# 3__Connectors___IO.net
KiCad netlist of a schematic drawn in Altium Designer
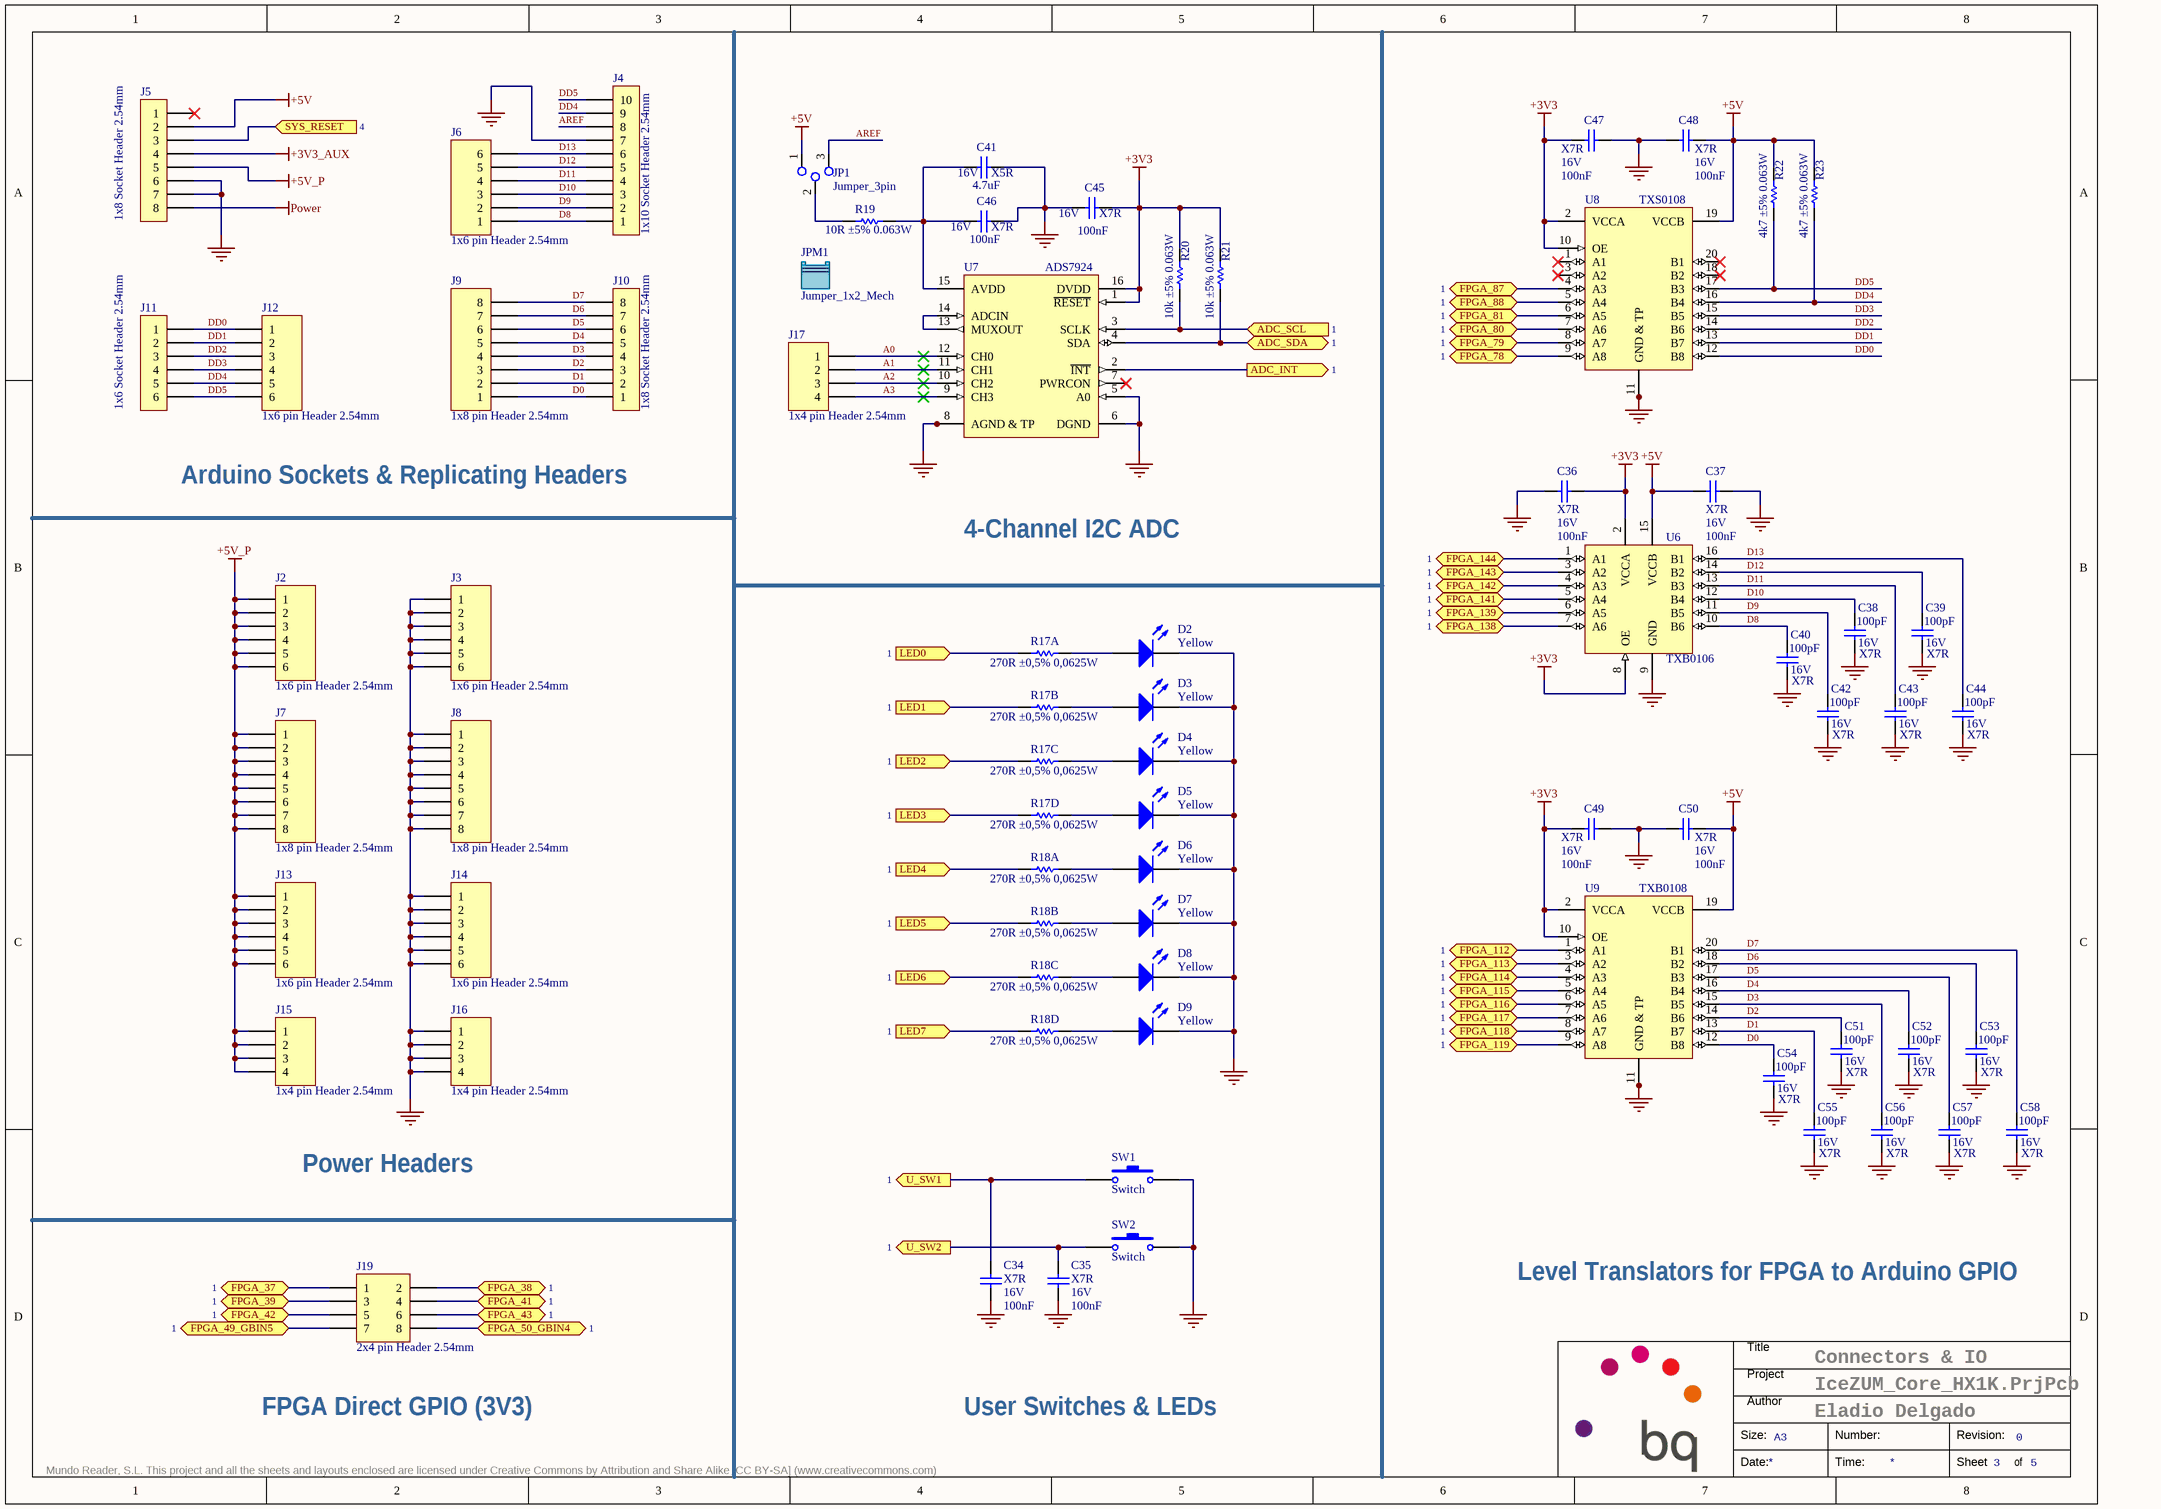
[diagram p0: [3]_Connectors_&_IO.SchDoc]

(export (version "E")
  (design (tool "Eeschema 10.0.6"))
  (components
    (comp (ref "C34")
      (value "Capacitor")
      (footprint "C0402")
      (description "Capacitor SMD")
      (fields
        (field (name "DIELECTRIC") "X7R")
        (field (name "VOLTAGE") "16V")
        (field (name "CAPACITANCE") "100nF")
        (field (name "PART NUMBER") "C0402_100nF_16V_±10%")
        (field (name "TOLERANCE") "±10%")
      )
      (libsource (lib "Pasives_Capacitor_SMD") (part "Capacitor"))
    )
    (comp (ref "C35")
      (value "Capacitor")
      (footprint "C0402")
      (description "Capacitor SMD")
      (fields
        (field (name "DIELECTRIC") "X7R")
        (field (name "VOLTAGE") "16V")
        (field (name "CAPACITANCE") "100nF")
        (field (name "PART NUMBER") "C0402_100nF_16V_±10%")
        (field (name "TOLERANCE") "±10%")
      )
      (libsource (lib "Pasives_Capacitor_SMD") (part "Capacitor"))
    )
    (comp (ref "C36")
      (value "Capacitor")
      (footprint "C0402")
      (description "Capacitor SMD")
      (fields
        (field (name "DIELECTRIC") "X7R")
        (field (name "VOLTAGE") "16V")
        (field (name "CAPACITANCE") "100nF")
        (field (name "PART NUMBER") "C0402_100nF_16V_±10%")
        (field (name "TOLERANCE") "±10%")
      )
      (libsource (lib "Pasives_Capacitor_SMD") (part "Capacitor"))
    )
    (comp (ref "C37")
      (value "Capacitor")
      (footprint "C0402")
      (description "Capacitor SMD")
      (fields
        (field (name "DIELECTRIC") "X7R")
        (field (name "VOLTAGE") "16V")
        (field (name "CAPACITANCE") "100nF")
        (field (name "PART NUMBER") "C0402_100nF_16V_±10%")
        (field (name "TOLERANCE") "±10%")
      )
      (libsource (lib "Pasives_Capacitor_SMD") (part "Capacitor"))
    )
    (comp (ref "C38")
      (value "Capacitor")
      (footprint "C0402")
      (description "Capacitor SMD")
      (fields
        (field (name "DIELECTRIC") "X7R")
        (field (name "VOLTAGE") "16V")
        (field (name "CAPACITANCE") "100pF")
        (field (name "PART NUMBER") "C0402_100pF_16V_±10%")
        (field (name "TOLERANCE") "±10%")
      )
      (libsource (lib "Pasives_Capacitor_SMD") (part "Capacitor"))
    )
    (comp (ref "C39")
      (value "Capacitor")
      (footprint "C0402")
      (description "Capacitor SMD")
      (fields
        (field (name "DIELECTRIC") "X7R")
        (field (name "VOLTAGE") "16V")
        (field (name "CAPACITANCE") "100pF")
        (field (name "PART NUMBER") "C0402_100pF_16V_±10%")
        (field (name "TOLERANCE") "±10%")
      )
      (libsource (lib "Pasives_Capacitor_SMD") (part "Capacitor"))
    )
    (comp (ref "C40")
      (value "Capacitor")
      (footprint "C0402")
      (description "Capacitor SMD")
      (fields
        (field (name "DIELECTRIC") "X7R")
        (field (name "VOLTAGE") "16V")
        (field (name "CAPACITANCE") "100pF")
        (field (name "PART NUMBER") "C0402_100pF_16V_±10%")
        (field (name "TOLERANCE") "±10%")
      )
      (libsource (lib "Pasives_Capacitor_SMD") (part "Capacitor"))
    )
    (comp (ref "C41")
      (value "Capacitor")
      (footprint "C0603")
      (description "Capacitor SMD")
      (fields
        (field (name "DIELECTRIC") "X5R")
        (field (name "VOLTAGE") "16V")
        (field (name "CAPACITANCE") "4.7uF")
        (field (name "PART NUMBER") "C0603_4.7uF_16V_±10%")
        (field (name "TOLERANCE") "±10%")
      )
      (libsource (lib "Pasives_Capacitor_SMD") (part "Capacitor"))
    )
    (comp (ref "C42")
      (value "Capacitor")
      (footprint "C0402")
      (description "Capacitor SMD")
      (fields
        (field (name "DIELECTRIC") "X7R")
        (field (name "VOLTAGE") "16V")
        (field (name "CAPACITANCE") "100pF")
        (field (name "PART NUMBER") "C0402_100pF_16V_±10%")
        (field (name "TOLERANCE") "±10%")
      )
      (libsource (lib "Pasives_Capacitor_SMD") (part "Capacitor"))
    )
    (comp (ref "C43")
      (value "Capacitor")
      (footprint "C0402")
      (description "Capacitor SMD")
      (fields
        (field (name "DIELECTRIC") "X7R")
        (field (name "VOLTAGE") "16V")
        (field (name "CAPACITANCE") "100pF")
        (field (name "PART NUMBER") "C0402_100pF_16V_±10%")
        (field (name "TOLERANCE") "±10%")
      )
      (libsource (lib "Pasives_Capacitor_SMD") (part "Capacitor"))
    )
    (comp (ref "C44")
      (value "Capacitor")
      (footprint "C0402")
      (description "Capacitor SMD")
      (fields
        (field (name "DIELECTRIC") "X7R")
        (field (name "VOLTAGE") "16V")
        (field (name "CAPACITANCE") "100pF")
        (field (name "PART NUMBER") "C0402_100pF_16V_±10%")
        (field (name "TOLERANCE") "±10%")
      )
      (libsource (lib "Pasives_Capacitor_SMD") (part "Capacitor"))
    )
    (comp (ref "C45")
      (value "Capacitor")
      (footprint "C0402")
      (description "Capacitor SMD")
      (fields
        (field (name "DIELECTRIC") "X7R")
        (field (name "VOLTAGE") "16V")
        (field (name "CAPACITANCE") "100nF")
        (field (name "PART NUMBER") "C0402_100nF_16V_±10%")
        (field (name "TOLERANCE") "±10%")
      )
      (libsource (lib "Pasives_Capacitor_SMD") (part "Capacitor"))
    )
    (comp (ref "C46")
      (value "Capacitor")
      (footprint "C0402")
      (description "Capacitor SMD")
      (fields
        (field (name "DIELECTRIC") "X7R")
        (field (name "VOLTAGE") "16V")
        (field (name "CAPACITANCE") "100nF")
        (field (name "PART NUMBER") "C0402_100nF_16V_±10%")
        (field (name "TOLERANCE") "±10%")
      )
      (libsource (lib "Pasives_Capacitor_SMD") (part "Capacitor"))
    )
    (comp (ref "C47")
      (value "Capacitor")
      (footprint "C0402")
      (description "Capacitor SMD")
      (fields
        (field (name "DIELECTRIC") "X7R")
        (field (name "VOLTAGE") "16V")
        (field (name "CAPACITANCE") "100nF")
        (field (name "PART NUMBER") "C0402_100nF_16V_±10%")
        (field (name "TOLERANCE") "±10%")
      )
      (libsource (lib "Pasives_Capacitor_SMD") (part "Capacitor"))
    )
    (comp (ref "C48")
      (value "Capacitor")
      (footprint "C0402")
      (description "Capacitor SMD")
      (fields
        (field (name "DIELECTRIC") "X7R")
        (field (name "VOLTAGE") "16V")
        (field (name "CAPACITANCE") "100nF")
        (field (name "PART NUMBER") "C0402_100nF_16V_±10%")
        (field (name "TOLERANCE") "±10%")
      )
      (libsource (lib "Pasives_Capacitor_SMD") (part "Capacitor"))
    )
    (comp (ref "C49")
      (value "Capacitor")
      (footprint "C0402")
      (description "Capacitor SMD")
      (fields
        (field (name "DIELECTRIC") "X7R")
        (field (name "VOLTAGE") "16V")
        (field (name "CAPACITANCE") "100nF")
        (field (name "PART NUMBER") "C0402_100nF_16V_±10%")
        (field (name "TOLERANCE") "±10%")
      )
      (libsource (lib "Pasives_Capacitor_SMD") (part "Capacitor"))
    )
    (comp (ref "C50")
      (value "Capacitor")
      (footprint "C0402")
      (description "Capacitor SMD")
      (fields
        (field (name "DIELECTRIC") "X7R")
        (field (name "VOLTAGE") "16V")
        (field (name "CAPACITANCE") "100nF")
        (field (name "PART NUMBER") "C0402_100nF_16V_±10%")
        (field (name "TOLERANCE") "±10%")
      )
      (libsource (lib "Pasives_Capacitor_SMD") (part "Capacitor"))
    )
    (comp (ref "C51")
      (value "Capacitor")
      (footprint "C0402")
      (description "Capacitor SMD")
      (fields
        (field (name "DIELECTRIC") "X7R")
        (field (name "VOLTAGE") "16V")
        (field (name "CAPACITANCE") "100pF")
        (field (name "PART NUMBER") "C0402_100pF_16V_±10%")
        (field (name "TOLERANCE") "±10%")
      )
      (libsource (lib "Pasives_Capacitor_SMD") (part "Capacitor"))
    )
    (comp (ref "C52")
      (value "Capacitor")
      (footprint "C0402")
      (description "Capacitor SMD")
      (fields
        (field (name "DIELECTRIC") "X7R")
        (field (name "VOLTAGE") "16V")
        (field (name "CAPACITANCE") "100pF")
        (field (name "PART NUMBER") "C0402_100pF_16V_±10%")
        (field (name "TOLERANCE") "±10%")
      )
      (libsource (lib "Pasives_Capacitor_SMD") (part "Capacitor"))
    )
    (comp (ref "C53")
      (value "Capacitor")
      (footprint "C0402")
      (description "Capacitor SMD")
      (fields
        (field (name "DIELECTRIC") "X7R")
        (field (name "VOLTAGE") "16V")
        (field (name "CAPACITANCE") "100pF")
        (field (name "PART NUMBER") "C0402_100pF_16V_±10%")
        (field (name "TOLERANCE") "±10%")
      )
      (libsource (lib "Pasives_Capacitor_SMD") (part "Capacitor"))
    )
    (comp (ref "C54")
      (value "Capacitor")
      (footprint "C0402")
      (description "Capacitor SMD")
      (fields
        (field (name "DIELECTRIC") "X7R")
        (field (name "VOLTAGE") "16V")
        (field (name "CAPACITANCE") "100pF")
        (field (name "PART NUMBER") "C0402_100pF_16V_±10%")
        (field (name "TOLERANCE") "±10%")
      )
      (libsource (lib "Pasives_Capacitor_SMD") (part "Capacitor"))
    )
    (comp (ref "C55")
      (value "Capacitor")
      (footprint "C0402")
      (description "Capacitor SMD")
      (fields
        (field (name "DIELECTRIC") "X7R")
        (field (name "VOLTAGE") "16V")
        (field (name "CAPACITANCE") "100pF")
        (field (name "PART NUMBER") "C0402_100pF_16V_±10%")
        (field (name "TOLERANCE") "±10%")
      )
      (libsource (lib "Pasives_Capacitor_SMD") (part "Capacitor"))
    )
    (comp (ref "C56")
      (value "Capacitor")
      (footprint "C0402")
      (description "Capacitor SMD")
      (fields
        (field (name "DIELECTRIC") "X7R")
        (field (name "VOLTAGE") "16V")
        (field (name "CAPACITANCE") "100pF")
        (field (name "PART NUMBER") "C0402_100pF_16V_±10%")
        (field (name "TOLERANCE") "±10%")
      )
      (libsource (lib "Pasives_Capacitor_SMD") (part "Capacitor"))
    )
    (comp (ref "C57")
      (value "Capacitor")
      (footprint "C0402")
      (description "Capacitor SMD")
      (fields
        (field (name "DIELECTRIC") "X7R")
        (field (name "VOLTAGE") "16V")
        (field (name "CAPACITANCE") "100pF")
        (field (name "PART NUMBER") "C0402_100pF_16V_±10%")
        (field (name "TOLERANCE") "±10%")
      )
      (libsource (lib "Pasives_Capacitor_SMD") (part "Capacitor"))
    )
    (comp (ref "C58")
      (value "Capacitor")
      (footprint "C0402")
      (description "Capacitor SMD")
      (fields
        (field (name "DIELECTRIC") "X7R")
        (field (name "VOLTAGE") "16V")
        (field (name "CAPACITANCE") "100pF")
        (field (name "PART NUMBER") "C0402_100pF_16V_±10%")
        (field (name "TOLERANCE") "±10%")
      )
      (libsource (lib "Pasives_Capacitor_SMD") (part "Capacitor"))
    )
    (comp (ref "D2")
      (value "Yellow")
      (footprint "LED0603")
      (description "LED")
      (fields (field (name "PART NUMBER") "LY Q971-H1L2-36") (field (name "MANUFACTURER") "OSRAM Opto"))
      (libsource (lib "Optoelectronics") (part "LED"))
    )
    (comp (ref "D3")
      (value "Yellow")
      (footprint "LED0603")
      (description "LED")
      (fields (field (name "PART NUMBER") "LY Q971-H1L2-36") (field (name "MANUFACTURER") "OSRAM Opto"))
      (libsource (lib "Optoelectronics") (part "LED"))
    )
    (comp (ref "D4")
      (value "Yellow")
      (footprint "LED0603")
      (description "LED")
      (fields (field (name "PART NUMBER") "LY Q971-H1L2-36") (field (name "MANUFACTURER") "OSRAM Opto"))
      (libsource (lib "Optoelectronics") (part "LED"))
    )
    (comp (ref "D5")
      (value "Yellow")
      (footprint "LED0603")
      (description "LED")
      (fields (field (name "PART NUMBER") "LY Q971-H1L2-36") (field (name "MANUFACTURER") "OSRAM Opto"))
      (libsource (lib "Optoelectronics") (part "LED"))
    )
    (comp (ref "D6")
      (value "Yellow")
      (footprint "LED0603")
      (description "LED")
      (fields (field (name "PART NUMBER") "LY Q971-H1L2-36") (field (name "MANUFACTURER") "OSRAM Opto"))
      (libsource (lib "Optoelectronics") (part "LED"))
    )
    (comp (ref "D7")
      (value "Yellow")
      (footprint "LED0603")
      (description "LED")
      (fields (field (name "PART NUMBER") "LY Q971-H1L2-36") (field (name "MANUFACTURER") "OSRAM Opto"))
      (libsource (lib "Optoelectronics") (part "LED"))
    )
    (comp (ref "D8")
      (value "Yellow")
      (footprint "LED0603")
      (description "LED")
      (fields (field (name "PART NUMBER") "LY Q971-H1L2-36") (field (name "MANUFACTURER") "OSRAM Opto"))
      (libsource (lib "Optoelectronics") (part "LED"))
    )
    (comp (ref "D9")
      (value "Yellow")
      (footprint "LED0603")
      (description "LED")
      (fields (field (name "PART NUMBER") "LY Q971-H1L2-36") (field (name "MANUFACTURER") "OSRAM Opto"))
      (libsource (lib "Optoelectronics") (part "LED"))
    )
    (comp (ref "J2")
      (value "1x6 pin Header 2.54mm")
      (footprint "1x6 Pin Header 2.54")
      (fields (field (name "MANUFACTURER") "Samtec") (field (name "PART NUMBER") "CON_PH_THT2.54_6 Red"))
      (libsource (lib "Conectores_PinHeader_2.54") (part "1x6 pin Header 2.54mm"))
    )
    (comp (ref "J3")
      (value "1x6 pin Header 2.54mm")
      (footprint "1x6 Pin Header 2.54")
      (fields (field (name "MANUFACTURER") "Samtec") (field (name "PART NUMBER") "CON_PH_THT2.54_6"))
      (libsource (lib "Conectores_PinHeader_2.54") (part "1x6 pin Header 2.54mm"))
    )
    (comp (ref "J4")
      (value "1x10 Socket Header 2.54mm")
      (footprint "1x10 Socket Header THT 2.54mm")
      (description "Connector, 10 pin Socket Header 2.54mm")
      (fields (field (name "MANUFACTURER") "Samtec") (field (name "PART NUMBER") "CON_SH_THT2.54_10"))
      (libsource (lib "Conectores_SocketHeader_2.54") (part "1x10 Socket Header 2.54mm"))
    )
    (comp (ref "J5")
      (value "1x8 Socket Header 2.54mm")
      (footprint "1x8 Socket Header THT 2.54mm")
      (description "8 pin Socket Header 2.54mm")
      (fields (field (name "MANUFACTURER") "Samtec") (field (name "PART NUMBER") "CON_SH_THT2.54_8"))
      (libsource (lib "Conectores_SocketHeader_2.54") (part "1x8 Socket Header 2.54mm"))
    )
    (comp (ref "J6")
      (value "1x6 pin Header 2.54mm")
      (footprint "1x6 Pin Header 2.54")
      (fields (field (name "MANUFACTURER") "Samtec") (field (name "PART NUMBER") "CON_PH_THT2.54_6 Natural"))
      (libsource (lib "") (part "1x6 pin Header 2.54mm_1"))
    )
    (comp (ref "J7")
      (value "1x8 pin Header 2.54mm")
      (footprint "1x8 Pin Header 2.54")
      (fields (field (name "MANUFACTURER") "Samtec") (field (name "PART NUMBER") "CON_PH_THT2.54_8 Red"))
      (libsource (lib "") (part "1x8 pin Header 2.54mm_1"))
    )
    (comp (ref "J8")
      (value "1x8 pin Header 2.54mm")
      (footprint "1x8 Pin Header 2.54")
      (fields (field (name "MANUFACTURER") "Samtec") (field (name "PART NUMBER") "CON_PH_THT2.54_8"))
      (libsource (lib "") (part "1x8 pin Header 2.54mm_1"))
    )
    (comp (ref "J9")
      (value "1x8 pin Header 2.54mm")
      (footprint "1x8 Pin Header 2.54")
      (fields (field (name "MANUFACTURER") "Samtec") (field (name "PART NUMBER") "CON_PH_THT2.54_8 Natural"))
      (libsource (lib "Conectores_PinHeader_2.54") (part "1x8 pin Header 2.54mm"))
    )
    (comp (ref "J10")
      (value "1x8 Socket Header 2.54mm")
      (footprint "1x8 Socket Header THT 2.54mm")
      (description "8 pin Socket Header 2.54mm")
      (fields (field (name "MANUFACTURER") "Samtec") (field (name "PART NUMBER") "CON_SH_THT2.54_8"))
      (libsource (lib "") (part "1x8 Socket Header 2.54mm_1"))
    )
    (comp (ref "J11")
      (value "1x6 Socket Header 2.54mm")
      (footprint "1x6 Socket Header THT 2.54mm")
      (description "6 pin Socket Header 2.54mm")
      (fields (field (name "MANUFACTURER") "Samtec") (field (name "PART NUMBER") "CON_SH_THT2.54_6"))
      (libsource (lib "Conectores_SocketHeader_2.54") (part "1x6 Socket Header 2.54mm"))
    )
    (comp (ref "J12")
      (value "1x6 pin Header 2.54mm")
      (footprint "1x6 Pin Header 2.54")
      (description "Connector, 1x6 pin Header 2.54mm")
      (fields (field (name "MANUFACTURER") "Samtec") (field (name "PART NUMBER") "CON_PH_THT2.54_6 Natural"))
      (libsource (lib "Conectores_PinHeader_2.54") (part "1x6 pin Header 2.54mm"))
    )
    (comp (ref "J13")
      (value "1x6 pin Header 2.54mm")
      (footprint "1x6 Pin Header 2.54")
      (fields (field (name "MANUFACTURER") "Samtec") (field (name "PART NUMBER") "CON_PH_THT2.54_6 Red"))
      (libsource (lib "Conectores_PinHeader_2.54") (part "1x6 pin Header 2.54mm"))
    )
    (comp (ref "J14")
      (value "1x6 pin Header 2.54mm")
      (footprint "1x6 Pin Header 2.54")
      (fields (field (name "MANUFACTURER") "Samtec") (field (name "PART NUMBER") "CON_PH_THT2.54_6"))
      (libsource (lib "Conectores_PinHeader_2.54") (part "1x6 pin Header 2.54mm"))
    )
    (comp (ref "J15")
      (value "1x4 pin Header 2.54mm")
      (footprint "1x4 Pin Header 2.54")
      (description "Connector, 1x4 pin Header 2.54mm")
      (fields (field (name "MANUFACTURER") "Samtec") (field (name "PART NUMBER") "CON_PH_THT2.54_4 Red"))
      (libsource (lib "Conectores_PinHeader_2.54") (part "1x4 pin Header 2.54mm"))
    )
    (comp (ref "J16")
      (value "1x4 pin Header 2.54mm")
      (footprint "1x4 Pin Header 2.54")
      (description "Connector, 1x4 pin Header 2.54mm")
      (fields (field (name "MANUFACTURER") "Samtec") (field (name "PART NUMBER") "CON_PH_THT2.54_4"))
      (libsource (lib "Conectores_PinHeader_2.54") (part "1x4 pin Header 2.54mm"))
    )
    (comp (ref "J17")
      (value "1x4 pin Header 2.54mm")
      (footprint "1x4 Pin Header 2.54")
      (description "Connector, 1x4 pin Header 2.54mm")
      (fields (field (name "MANUFACTURER") "Samtec") (field (name "PART NUMBER") "CON_PH_THT2.54_4 Blue"))
      (libsource (lib "") (part "1x4 pin Header 2.54mm_1"))
    )
    (comp (ref "J19")
      (value "2x4 pin Header 2.54mm")
      (footprint "2x4 Pin Header 2.54")
      (description "Connector, 8 pin Dual Header 2.54mm")
      (fields (field (name "MANUFACTURER") "Samtec") (field (name "PART NUMBER") "CON_DPH_THT2.54_8"))
      (libsource (lib "Conectores_PinHeader_2.54") (part "2x4 pin Header 2.54mm"))
    )
    (comp (ref "JP1")
      (value "Jumper_3pin")
      (footprint "1x3 Header 2.54")
      (description "Connector, Jumper, 3 pin Male Header 2.54mm")
      (fields (field (name "PART NUMBER") "Jumper_3pin_THT") (field (name "MANUFACTURER") "Würth"))
      (libsource (lib "Connectors_Jumpers") (part "Jumper_3pin"))
    )
    (comp (ref "JPM1")
      (value "Jumper_1x2_Mech")
      (description "Connector, Jumper, 1x2 Jumper 2.54mm")
      (fields (field (name "PART NUMBER") "Jumper_2pin_Mech") (field (name "MANUFACTURER") "Würth"))
      (libsource (lib "Connectors_Jumpers") (part "Jumper_1x2_Mech"))
    )
    (comp (ref "R17")
      (value "270R ±0,5% 0,0625W")
      (footprint "4xArray_1206")
      (description "Resistor")
      (fields (field (name "TOLERANCE") "±0,5%") (field (name "POWER") "0,0625W"))
      (libsource (lib "Pasives_Resistor_SMD") (part "Resistor_x4_Parts"))
    )
    (comp (ref "R18")
      (value "270R ±0,5% 0,0625W")
      (footprint "4xArray_1206")
      (description "Resistor")
      (fields (field (name "TOLERANCE") "±0,5%") (field (name "POWER") "0,0625W"))
      (libsource (lib "Pasives_Resistor_SMD") (part "Resistor_x4_Parts"))
    )
    (comp (ref "R19")
      (value "10R ±5% 0.063W")
      (footprint "R0402")
      (description "Resistor, SMD")
      (fields (field (name "TOLERANCE") "±5%") (field (name "POWER") "0.063W"))
      (libsource (lib "Pasives_Resistor_SMD") (part "Resistor"))
    )
    (comp (ref "R20")
      (value "10k ±5% 0.063W")
      (footprint "R0402")
      (description "Resistor, SMD")
      (fields (field (name "TOLERANCE") "±5%") (field (name "POWER") "0.063W"))
      (libsource (lib "Pasives_Resistor_SMD") (part "Resistor"))
    )
    (comp (ref "R21")
      (value "10k ±5% 0.063W")
      (footprint "R0402")
      (description "Resistor, SMD")
      (fields (field (name "TOLERANCE") "±5%") (field (name "POWER") "0.063W"))
      (libsource (lib "Pasives_Resistor_SMD") (part "Resistor"))
    )
    (comp (ref "R22")
      (value "4k7 ±5% 0.063W")
      (footprint "R0402")
      (description "Resistor, SMD")
      (fields (field (name "TOLERANCE") "±5%") (field (name "POWER") "0.063W"))
      (libsource (lib "Pasives_Resistor_SMD") (part "Resistor"))
    )
    (comp (ref "R23")
      (value "4k7 ±5% 0.063W")
      (footprint "R0402")
      (description "Resistor, SMD")
      (fields (field (name "TOLERANCE") "±5%") (field (name "POWER") "0.063W"))
      (libsource (lib "Pasives_Resistor_SMD") (part "Resistor"))
    )
    (comp (ref "SW1")
      (value "Switch")
      (footprint "SW_SMD_6.0x3.8")
      (description "Micro miniature pushbutton surface Switch")
      (fields (field (name "PART NUMBER") "SW SMD") (field (name "MANUFACTURER") "Würth Elektronik"))
      (libsource (lib "Electromechanical") (part "Switch"))
    )
    (comp (ref "SW2")
      (value "Switch")
      (footprint "SW_SMD_6.0x3.8")
      (description "Micro miniature pushbutton surface Switch")
      (fields (field (name "PART NUMBER") "SW SMD") (field (name "MANUFACTURER") "Würth Elektronik"))
      (libsource (lib "Electromechanical") (part "Switch"))
    )
    (comp (ref "U6")
      (value "TXB0106")
      (footprint "QFN16")
      (description "Voltage Translator, Hex")
      (fields (field (name "MANUFACTURER") "Texas Instruments"))
      (libsource (lib "Voltage_translator") (part "TXB0106"))
    )
    (comp (ref "U7")
      (value "ADS7924")
      (footprint "QFN16")
      (description "ADC Converter, 12-Bit, 4-Ch, I2C")
      (fields (field (name "MANUFACTURER") "Texas Instruments"))
      (libsource (lib "Data_Converters") (part "ADS7924"))
    )
    (comp (ref "U8")
      (value "TXS0108")
      (footprint "VQFN20 4.5x3.5mm")
      (description "Voltage Level Translator, 8-Bit Bidir., with TP")
      (fields (field (name "MANUFACTURER") "Texas Instruments"))
      (libsource (lib "Voltage_translator") (part "TXB0108RGY"))
    )
    (comp (ref "U9")
      (value "TXB0108")
      (footprint "VQFN20 4.5x3.5mm")
      (description "Voltage Level Translator, 8-Bit Bidir., with TP")
      (fields (field (name "MANUFACTURER") "Texas Instruments"))
      (libsource (lib "Voltage_translator") (part "TXB0108RGY"))
    )
  )
  (nets
    (net (code "1") (name "+3V3") (class "Default")
      (node (ref "C36") (pin "1") (pinfunction "1_1") (pintype "passive"))
      (node (ref "C45") (pin "2") (pinfunction "2_2") (pintype "passive"))
      (node (ref "C47") (pin "2") (pinfunction "2_2") (pintype "passive"))
      (node (ref "C49") (pin "2") (pinfunction "2_2") (pintype "passive"))
      (node (ref "R20") (pin "2") (pinfunction "2_2") (pintype "passive"))
      (node (ref "R21") (pin "2") (pinfunction "2_2") (pintype "passive"))
      (node (ref "U6") (pin "2") (pinfunction "VCCA_2") (pintype "power_in"))
      (node (ref "U6") (pin "8") (pinfunction "OE_8") (pintype "input"))
      (node (ref "U7") (pin "1") (pinfunction "RESET_1") (pintype "input"))
      (node (ref "U7") (pin "16") (pinfunction "DVDD_16") (pintype "power_in"))
      (node (ref "U8") (pin "10") (pinfunction "OE_10") (pintype "input"))
      (node (ref "U8") (pin "2") (pinfunction "VCCA_2") (pintype "power_in"))
      (node (ref "U9") (pin "10") (pinfunction "OE_10") (pintype "input"))
      (node (ref "U9") (pin "2") (pinfunction "VCCA_2") (pintype "power_in"))
    )
    (net (code "2") (name "+3V3_AUX") (class "Default")
      (node (ref "J5") (pin "4") (pinfunction "4_4") (pintype "passive"))
    )
    (net (code "3") (name "+5V") (class "Default")
      (node (ref "C37") (pin "2") (pinfunction "2_2") (pintype "passive"))
      (node (ref "C48") (pin "1") (pinfunction "1_1") (pintype "passive"))
      (node (ref "C50") (pin "1") (pinfunction "1_1") (pintype "passive"))
      (node (ref "J5") (pin "2") (pinfunction "2_2") (pintype "passive"))
      (node (ref "JP1") (pin "1") (pinfunction "1_1") (pintype "passive"))
      (node (ref "R22") (pin "2") (pinfunction "2_2") (pintype "passive"))
      (node (ref "R23") (pin "2") (pinfunction "2_2") (pintype "passive"))
      (node (ref "U6") (pin "15") (pinfunction "VCCB_15") (pintype "power_in"))
      (node (ref "U8") (pin "19") (pinfunction "VCCB_19") (pintype "power_in"))
      (node (ref "U9") (pin "19") (pinfunction "VCCB_19") (pintype "power_in"))
    )
    (net (code "4") (name "+5V_P") (class "Default")
      (node (ref "J13") (pin "1") (pinfunction "1_1") (pintype "passive"))
      (node (ref "J13") (pin "2") (pinfunction "2_2") (pintype "passive"))
      (node (ref "J13") (pin "3") (pinfunction "3_3") (pintype "passive"))
      (node (ref "J13") (pin "4") (pinfunction "4_4") (pintype "passive"))
      (node (ref "J13") (pin "5") (pinfunction "5_5") (pintype "passive"))
      (node (ref "J13") (pin "6") (pinfunction "6_6") (pintype "passive"))
      (node (ref "J15") (pin "1") (pinfunction "1_1") (pintype "passive"))
      (node (ref "J15") (pin "2") (pinfunction "2_2") (pintype "passive"))
      (node (ref "J15") (pin "3") (pinfunction "3_3") (pintype "passive"))
      (node (ref "J15") (pin "4") (pinfunction "4_4") (pintype "passive"))
      (node (ref "J2") (pin "1") (pinfunction "1_1") (pintype "passive"))
      (node (ref "J2") (pin "2") (pinfunction "2_2") (pintype "passive"))
      (node (ref "J2") (pin "3") (pinfunction "3_3") (pintype "passive"))
      (node (ref "J2") (pin "4") (pinfunction "4_4") (pintype "passive"))
      (node (ref "J2") (pin "5") (pinfunction "5_5") (pintype "passive"))
      (node (ref "J2") (pin "6") (pinfunction "6_6") (pintype "passive"))
      (node (ref "J5") (pin "5") (pinfunction "5_5") (pintype "passive"))
      (node (ref "J7") (pin "1") (pinfunction "1_1") (pintype "passive"))
      (node (ref "J7") (pin "2") (pinfunction "2_2") (pintype "passive"))
      (node (ref "J7") (pin "3") (pinfunction "3_3") (pintype "passive"))
      (node (ref "J7") (pin "4") (pinfunction "4_4") (pintype "passive"))
      (node (ref "J7") (pin "5") (pinfunction "5_5") (pintype "passive"))
      (node (ref "J7") (pin "6") (pinfunction "6_6") (pintype "passive"))
      (node (ref "J7") (pin "7") (pinfunction "7_7") (pintype "passive"))
      (node (ref "J7") (pin "8") (pinfunction "8_8") (pintype "passive"))
    )
    (net (code "5") (name "/A0") (class "Default")
      (node (ref "J17") (pin "1") (pinfunction "1_1") (pintype "passive"))
      (node (ref "U7") (pin "12") (pinfunction "CH0_12") (pintype "input"))
    )
    (net (code "6") (name "/A1") (class "Default")
      (node (ref "J17") (pin "2") (pinfunction "2_2") (pintype "passive"))
      (node (ref "U7") (pin "11") (pinfunction "CH1_11") (pintype "input"))
    )
    (net (code "7") (name "/A2") (class "Default")
      (node (ref "J17") (pin "3") (pinfunction "3_3") (pintype "passive"))
      (node (ref "U7") (pin "10") (pinfunction "CH2_10") (pintype "input"))
    )
    (net (code "8") (name "/A3") (class "Default")
      (node (ref "J17") (pin "4") (pinfunction "4_4") (pintype "passive"))
      (node (ref "U7") (pin "9") (pinfunction "CH3_9") (pintype "input"))
    )
    (net (code "9") (name "/ADC_INT") (class "Default")
      (node (ref "U7") (pin "2") (pinfunction "INT_2") (pintype "output"))
    )
    (net (code "10") (name "/ADC_SCL") (class "Default")
      (node (ref "R20") (pin "1") (pinfunction "1_1") (pintype "passive"))
      (node (ref "U7") (pin "3") (pinfunction "SCLK_3") (pintype "input"))
    )
    (net (code "11") (name "/ADC_SDA") (class "Default")
      (node (ref "R21") (pin "1") (pinfunction "1_1") (pintype "passive"))
      (node (ref "U7") (pin "4") (pinfunction "SDA_4") (pintype "bidirectional"))
    )
    (net (code "12") (name "/AREF") (class "Default")
      (node (ref "J4") (pin "8") (pinfunction "8_8") (pintype "passive"))
      (node (ref "JP1") (pin "3") (pinfunction "3_3") (pintype "passive"))
    )
    (net (code "13") (name "/D0") (class "Default")
      (node (ref "C54") (pin "2") (pinfunction "2_2") (pintype "passive"))
      (node (ref "J10") (pin "1") (pinfunction "1_1") (pintype "passive"))
      (node (ref "J9") (pin "1") (pinfunction "1_1") (pintype "passive"))
      (node (ref "U9") (pin "12") (pinfunction "B8_12") (pintype "bidirectional"))
    )
    (net (code "14") (name "/D1") (class "Default")
      (node (ref "C55") (pin "2") (pinfunction "2_2") (pintype "passive"))
      (node (ref "J10") (pin "2") (pinfunction "2_2") (pintype "passive"))
      (node (ref "J9") (pin "2") (pinfunction "2_2") (pintype "passive"))
      (node (ref "U9") (pin "13") (pinfunction "B7_13") (pintype "bidirectional"))
    )
    (net (code "15") (name "/D2") (class "Default")
      (node (ref "C51") (pin "2") (pinfunction "2_2") (pintype "passive"))
      (node (ref "J10") (pin "3") (pinfunction "3_3") (pintype "passive"))
      (node (ref "J9") (pin "3") (pinfunction "3_3") (pintype "passive"))
      (node (ref "U9") (pin "14") (pinfunction "B6_14") (pintype "bidirectional"))
    )
    (net (code "16") (name "/D3") (class "Default")
      (node (ref "C56") (pin "2") (pinfunction "2_2") (pintype "passive"))
      (node (ref "J10") (pin "4") (pinfunction "4_4") (pintype "passive"))
      (node (ref "J9") (pin "4") (pinfunction "4_4") (pintype "passive"))
      (node (ref "U9") (pin "15") (pinfunction "B5_15") (pintype "bidirectional"))
    )
    (net (code "17") (name "/D4") (class "Default")
      (node (ref "C52") (pin "2") (pinfunction "2_2") (pintype "passive"))
      (node (ref "J10") (pin "5") (pinfunction "5_5") (pintype "passive"))
      (node (ref "J9") (pin "5") (pinfunction "5_5") (pintype "passive"))
      (node (ref "U9") (pin "16") (pinfunction "B4_16") (pintype "bidirectional"))
    )
    (net (code "18") (name "/D5") (class "Default")
      (node (ref "C57") (pin "2") (pinfunction "2_2") (pintype "passive"))
      (node (ref "J10") (pin "6") (pinfunction "6_6") (pintype "passive"))
      (node (ref "J9") (pin "6") (pinfunction "6_6") (pintype "passive"))
      (node (ref "U9") (pin "17") (pinfunction "B3_17") (pintype "bidirectional"))
    )
    (net (code "19") (name "/D6") (class "Default")
      (node (ref "C53") (pin "2") (pinfunction "2_2") (pintype "passive"))
      (node (ref "J10") (pin "7") (pinfunction "7_7") (pintype "passive"))
      (node (ref "J9") (pin "7") (pinfunction "7_7") (pintype "passive"))
      (node (ref "U9") (pin "18") (pinfunction "B2_18") (pintype "bidirectional"))
    )
    (net (code "20") (name "/D7") (class "Default")
      (node (ref "C58") (pin "2") (pinfunction "2_2") (pintype "passive"))
      (node (ref "J10") (pin "8") (pinfunction "8_8") (pintype "passive"))
      (node (ref "J9") (pin "8") (pinfunction "8_8") (pintype "passive"))
      (node (ref "U9") (pin "20") (pinfunction "B1_20") (pintype "bidirectional"))
    )
    (net (code "21") (name "/D8") (class "Default")
      (node (ref "C40") (pin "2") (pinfunction "2_2") (pintype "passive"))
      (node (ref "J4") (pin "1") (pinfunction "1_1") (pintype "passive"))
      (node (ref "J6") (pin "1") (pinfunction "1_1") (pintype "passive"))
      (node (ref "U6") (pin "10") (pinfunction "B6_10") (pintype "bidirectional"))
    )
    (net (code "22") (name "/D9") (class "Default")
      (node (ref "C42") (pin "2") (pinfunction "2_2") (pintype "passive"))
      (node (ref "J4") (pin "2") (pinfunction "2_2") (pintype "passive"))
      (node (ref "J6") (pin "2") (pinfunction "2_2") (pintype "passive"))
      (node (ref "U6") (pin "11") (pinfunction "B5_11") (pintype "bidirectional"))
    )
    (net (code "23") (name "/D10") (class "Default")
      (node (ref "C38") (pin "2") (pinfunction "2_2") (pintype "passive"))
      (node (ref "J4") (pin "3") (pinfunction "3_3") (pintype "passive"))
      (node (ref "J6") (pin "3") (pinfunction "3_3") (pintype "passive"))
      (node (ref "U6") (pin "12") (pinfunction "B4_12") (pintype "bidirectional"))
    )
    (net (code "24") (name "/D11") (class "Default")
      (node (ref "C43") (pin "2") (pinfunction "2_2") (pintype "passive"))
      (node (ref "J4") (pin "4") (pinfunction "4_4") (pintype "passive"))
      (node (ref "J6") (pin "4") (pinfunction "4_4") (pintype "passive"))
      (node (ref "U6") (pin "13") (pinfunction "B3_13") (pintype "bidirectional"))
    )
    (net (code "25") (name "/D12") (class "Default")
      (node (ref "C39") (pin "2") (pinfunction "2_2") (pintype "passive"))
      (node (ref "J4") (pin "5") (pinfunction "5_5") (pintype "passive"))
      (node (ref "J6") (pin "5") (pinfunction "5_5") (pintype "passive"))
      (node (ref "U6") (pin "14") (pinfunction "B2_14") (pintype "bidirectional"))
    )
    (net (code "26") (name "/D13") (class "Default")
      (node (ref "C44") (pin "2") (pinfunction "2_2") (pintype "passive"))
      (node (ref "J4") (pin "6") (pinfunction "6_6") (pintype "passive"))
      (node (ref "J6") (pin "6") (pinfunction "6_6") (pintype "passive"))
      (node (ref "U6") (pin "16") (pinfunction "B1_16") (pintype "bidirectional"))
    )
    (net (code "27") (name "/DD0") (class "Default")
      (node (ref "J11") (pin "1") (pinfunction "1_1") (pintype "passive"))
      (node (ref "J12") (pin "1") (pinfunction "1_1") (pintype "passive"))
      (node (ref "U8") (pin "12") (pinfunction "B8_12") (pintype "bidirectional"))
    )
    (net (code "28") (name "/DD1") (class "Default")
      (node (ref "J11") (pin "2") (pinfunction "2_2") (pintype "passive"))
      (node (ref "J12") (pin "2") (pinfunction "2_2") (pintype "passive"))
      (node (ref "U8") (pin "13") (pinfunction "B7_13") (pintype "bidirectional"))
    )
    (net (code "29") (name "/DD2") (class "Default")
      (node (ref "J11") (pin "3") (pinfunction "3_3") (pintype "passive"))
      (node (ref "J12") (pin "3") (pinfunction "3_3") (pintype "passive"))
      (node (ref "U8") (pin "14") (pinfunction "B6_14") (pintype "bidirectional"))
    )
    (net (code "30") (name "/DD3") (class "Default")
      (node (ref "J11") (pin "4") (pinfunction "4_4") (pintype "passive"))
      (node (ref "J12") (pin "4") (pinfunction "4_4") (pintype "passive"))
      (node (ref "U8") (pin "15") (pinfunction "B5_15") (pintype "bidirectional"))
    )
    (net (code "31") (name "/DD4") (class "Default")
      (node (ref "J11") (pin "5") (pinfunction "5_5") (pintype "passive"))
      (node (ref "J12") (pin "5") (pinfunction "5_5") (pintype "passive"))
      (node (ref "J4") (pin "9") (pinfunction "9_9") (pintype "passive"))
      (node (ref "R23") (pin "1") (pinfunction "1_1") (pintype "passive"))
      (node (ref "U8") (pin "16") (pinfunction "B4_16") (pintype "bidirectional"))
    )
    (net (code "32") (name "/DD5") (class "Default")
      (node (ref "J11") (pin "6") (pinfunction "6_6") (pintype "passive"))
      (node (ref "J12") (pin "6") (pinfunction "6_6") (pintype "passive"))
      (node (ref "J4") (pin "10") (pinfunction "10_10") (pintype "passive"))
      (node (ref "R22") (pin "1") (pinfunction "1_1") (pintype "passive"))
      (node (ref "U8") (pin "17") (pinfunction "B3_17") (pintype "bidirectional"))
    )
    (net (code "33") (name "/FPGA_37") (class "Default")
      (node (ref "J19") (pin "1") (pinfunction "1_1") (pintype "passive"))
    )
    (net (code "34") (name "/FPGA_38") (class "Default")
      (node (ref "J19") (pin "2") (pinfunction "2_2") (pintype "passive"))
    )
    (net (code "35") (name "/FPGA_39") (class "Default")
      (node (ref "J19") (pin "3") (pinfunction "3_3") (pintype "passive"))
    )
    (net (code "36") (name "/FPGA_41") (class "Default")
      (node (ref "J19") (pin "4") (pinfunction "4_4") (pintype "passive"))
    )
    (net (code "37") (name "/FPGA_42") (class "Default")
      (node (ref "J19") (pin "5") (pinfunction "5_5") (pintype "passive"))
    )
    (net (code "38") (name "/FPGA_43") (class "Default")
      (node (ref "J19") (pin "6") (pinfunction "6_6") (pintype "passive"))
    )
    (net (code "39") (name "/FPGA_49_GBIN5") (class "Default")
      (node (ref "J19") (pin "7") (pinfunction "7_7") (pintype "passive"))
    )
    (net (code "40") (name "/FPGA_50_GBIN4") (class "Default")
      (node (ref "J19") (pin "8") (pinfunction "8_8") (pintype "passive"))
    )
    (net (code "41") (name "/FPGA_78") (class "Default")
      (node (ref "U8") (pin "9") (pinfunction "A8_9") (pintype "bidirectional"))
    )
    (net (code "42") (name "/FPGA_79") (class "Default")
      (node (ref "U8") (pin "8") (pinfunction "A7_8") (pintype "bidirectional"))
    )
    (net (code "43") (name "/FPGA_80") (class "Default")
      (node (ref "U8") (pin "7") (pinfunction "A6_7") (pintype "bidirectional"))
    )
    (net (code "44") (name "/FPGA_81") (class "Default")
      (node (ref "U8") (pin "6") (pinfunction "A5_6") (pintype "bidirectional"))
    )
    (net (code "45") (name "/FPGA_87") (class "Default")
      (node (ref "U8") (pin "4") (pinfunction "A3_4") (pintype "bidirectional"))
    )
    (net (code "46") (name "/FPGA_88") (class "Default")
      (node (ref "U8") (pin "5") (pinfunction "A4_5") (pintype "bidirectional"))
    )
    (net (code "47") (name "/FPGA_112") (class "Default")
      (node (ref "U9") (pin "1") (pinfunction "A1_1") (pintype "bidirectional"))
    )
    (net (code "48") (name "/FPGA_113") (class "Default")
      (node (ref "U9") (pin "3") (pinfunction "A2_3") (pintype "bidirectional"))
    )
    (net (code "49") (name "/FPGA_114") (class "Default")
      (node (ref "U9") (pin "4") (pinfunction "A3_4") (pintype "bidirectional"))
    )
    (net (code "50") (name "/FPGA_115") (class "Default")
      (node (ref "U9") (pin "5") (pinfunction "A4_5") (pintype "bidirectional"))
    )
    (net (code "51") (name "/FPGA_116") (class "Default")
      (node (ref "U9") (pin "6") (pinfunction "A5_6") (pintype "bidirectional"))
    )
    (net (code "52") (name "/FPGA_117") (class "Default")
      (node (ref "U9") (pin "7") (pinfunction "A6_7") (pintype "bidirectional"))
    )
    (net (code "53") (name "/FPGA_118") (class "Default")
      (node (ref "U9") (pin "8") (pinfunction "A7_8") (pintype "bidirectional"))
    )
    (net (code "54") (name "/FPGA_119") (class "Default")
      (node (ref "U9") (pin "9") (pinfunction "A8_9") (pintype "bidirectional"))
    )
    (net (code "55") (name "/FPGA_138") (class "Default")
      (node (ref "U6") (pin "7") (pinfunction "A6_7") (pintype "bidirectional"))
    )
    (net (code "56") (name "/FPGA_139") (class "Default")
      (node (ref "U6") (pin "6") (pinfunction "A5_6") (pintype "bidirectional"))
    )
    (net (code "57") (name "/FPGA_141") (class "Default")
      (node (ref "U6") (pin "5") (pinfunction "A4_5") (pintype "bidirectional"))
    )
    (net (code "58") (name "/FPGA_142") (class "Default")
      (node (ref "U6") (pin "4") (pinfunction "A3_4") (pintype "bidirectional"))
    )
    (net (code "59") (name "/FPGA_143") (class "Default")
      (node (ref "U6") (pin "3") (pinfunction "A2_3") (pintype "bidirectional"))
    )
    (net (code "60") (name "/FPGA_144") (class "Default")
      (node (ref "U6") (pin "1") (pinfunction "A1_1") (pintype "bidirectional"))
    )
    (net (code "61") (name "/LED0") (class "Default")
      (node (ref "R17") (pin "1") (pinfunction "1_1") (pintype "passive"))
    )
    (net (code "62") (name "/LED1") (class "Default")
      (node (ref "R17") (pin "2") (pinfunction "2_2") (pintype "passive"))
    )
    (net (code "63") (name "/LED2") (class "Default")
      (node (ref "R17") (pin "3") (pinfunction "3_3") (pintype "passive"))
    )
    (net (code "64") (name "/LED3") (class "Default")
      (node (ref "R17") (pin "4") (pinfunction "4_4") (pintype "passive"))
    )
    (net (code "65") (name "/LED4") (class "Default")
      (node (ref "R18") (pin "1") (pinfunction "1_1") (pintype "passive"))
    )
    (net (code "66") (name "/LED5") (class "Default")
      (node (ref "R18") (pin "2") (pinfunction "2_2") (pintype "passive"))
    )
    (net (code "67") (name "/LED6") (class "Default")
      (node (ref "R18") (pin "3") (pinfunction "3_3") (pintype "passive"))
    )
    (net (code "68") (name "/LED7") (class "Default")
      (node (ref "R18") (pin "4") (pinfunction "4_4") (pintype "passive"))
    )
    (net (code "69") (name "/SYS_RESET") (class "Default")
      (node (ref "J5") (pin "3") (pinfunction "3_3") (pintype "passive"))
    )
    (net (code "70") (name "/U_SW1") (class "Default")
      (node (ref "C34") (pin "2") (pinfunction "2_2") (pintype "passive"))
      (node (ref "SW1") (pin "1") (pinfunction "1_1") (pintype "passive"))
    )
    (net (code "71") (name "/U_SW2") (class "Default")
      (node (ref "C35") (pin "2") (pinfunction "2_2") (pintype "passive"))
      (node (ref "SW2") (pin "1") (pinfunction "1_1") (pintype "passive"))
    )
    (net (code "72") (name "GND") (class "Default")
      (node (ref "C34") (pin "1") (pinfunction "1_1") (pintype "passive"))
      (node (ref "C35") (pin "1") (pinfunction "1_1") (pintype "passive"))
      (node (ref "C36") (pin "2") (pinfunction "2_2") (pintype "passive"))
      (node (ref "C37") (pin "1") (pinfunction "1_1") (pintype "passive"))
      (node (ref "C38") (pin "1") (pinfunction "1_1") (pintype "passive"))
      (node (ref "C39") (pin "1") (pinfunction "1_1") (pintype "passive"))
      (node (ref "C40") (pin "1") (pinfunction "1_1") (pintype "passive"))
      (node (ref "C41") (pin "1") (pinfunction "1_1") (pintype "passive"))
      (node (ref "C42") (pin "1") (pinfunction "1_1") (pintype "passive"))
      (node (ref "C43") (pin "1") (pinfunction "1_1") (pintype "passive"))
      (node (ref "C44") (pin "1") (pinfunction "1_1") (pintype "passive"))
      (node (ref "C45") (pin "1") (pinfunction "1_1") (pintype "passive"))
      (node (ref "C46") (pin "2") (pinfunction "2_2") (pintype "passive"))
      (node (ref "C47") (pin "1") (pinfunction "1_1") (pintype "passive"))
      (node (ref "C48") (pin "2") (pinfunction "2_2") (pintype "passive"))
      (node (ref "C49") (pin "1") (pinfunction "1_1") (pintype "passive"))
      (node (ref "C50") (pin "2") (pinfunction "2_2") (pintype "passive"))
      (node (ref "C51") (pin "1") (pinfunction "1_1") (pintype "passive"))
      (node (ref "C52") (pin "1") (pinfunction "1_1") (pintype "passive"))
      (node (ref "C53") (pin "1") (pinfunction "1_1") (pintype "passive"))
      (node (ref "C54") (pin "1") (pinfunction "1_1") (pintype "passive"))
      (node (ref "C55") (pin "1") (pinfunction "1_1") (pintype "passive"))
      (node (ref "C56") (pin "1") (pinfunction "1_1") (pintype "passive"))
      (node (ref "C57") (pin "1") (pinfunction "1_1") (pintype "passive"))
      (node (ref "C58") (pin "1") (pinfunction "1_1") (pintype "passive"))
      (node (ref "D2") (pin "K") (pinfunction "K_K") (pintype "passive"))
      (node (ref "D3") (pin "K") (pinfunction "K_K") (pintype "passive"))
      (node (ref "D4") (pin "K") (pinfunction "K_K") (pintype "passive"))
      (node (ref "D5") (pin "K") (pinfunction "K_K") (pintype "passive"))
      (node (ref "D6") (pin "K") (pinfunction "K_K") (pintype "passive"))
      (node (ref "D7") (pin "K") (pinfunction "K_K") (pintype "passive"))
      (node (ref "D8") (pin "K") (pinfunction "K_K") (pintype "passive"))
      (node (ref "D9") (pin "K") (pinfunction "K_K") (pintype "passive"))
      (node (ref "J14") (pin "1") (pinfunction "1_1") (pintype "passive"))
      (node (ref "J14") (pin "2") (pinfunction "2_2") (pintype "passive"))
      (node (ref "J14") (pin "3") (pinfunction "3_3") (pintype "passive"))
      (node (ref "J14") (pin "4") (pinfunction "4_4") (pintype "passive"))
      (node (ref "J14") (pin "5") (pinfunction "5_5") (pintype "passive"))
      (node (ref "J14") (pin "6") (pinfunction "6_6") (pintype "passive"))
      (node (ref "J16") (pin "1") (pinfunction "1_1") (pintype "passive"))
      (node (ref "J16") (pin "2") (pinfunction "2_2") (pintype "passive"))
      (node (ref "J16") (pin "3") (pinfunction "3_3") (pintype "passive"))
      (node (ref "J16") (pin "4") (pinfunction "4_4") (pintype "passive"))
      (node (ref "J3") (pin "1") (pinfunction "1_1") (pintype "passive"))
      (node (ref "J3") (pin "2") (pinfunction "2_2") (pintype "passive"))
      (node (ref "J3") (pin "3") (pinfunction "3_3") (pintype "passive"))
      (node (ref "J3") (pin "4") (pinfunction "4_4") (pintype "passive"))
      (node (ref "J3") (pin "5") (pinfunction "5_5") (pintype "passive"))
      (node (ref "J3") (pin "6") (pinfunction "6_6") (pintype "passive"))
      (node (ref "J4") (pin "7") (pinfunction "7_7") (pintype "passive"))
      (node (ref "J5") (pin "6") (pinfunction "6_6") (pintype "passive"))
      (node (ref "J5") (pin "7") (pinfunction "7_7") (pintype "passive"))
      (node (ref "J8") (pin "1") (pinfunction "1_1") (pintype "passive"))
      (node (ref "J8") (pin "2") (pinfunction "2_2") (pintype "passive"))
      (node (ref "J8") (pin "3") (pinfunction "3_3") (pintype "passive"))
      (node (ref "J8") (pin "4") (pinfunction "4_4") (pintype "passive"))
      (node (ref "J8") (pin "5") (pinfunction "5_5") (pintype "passive"))
      (node (ref "J8") (pin "6") (pinfunction "6_6") (pintype "passive"))
      (node (ref "J8") (pin "7") (pinfunction "7_7") (pintype "passive"))
      (node (ref "J8") (pin "8") (pinfunction "8_8") (pintype "passive"))
      (node (ref "SW1") (pin "2") (pinfunction "2_2") (pintype "passive"))
      (node (ref "SW2") (pin "2") (pinfunction "2_2") (pintype "passive"))
      (node (ref "U6") (pin "9") (pinfunction "GND_9") (pintype "power_in"))
      (node (ref "U7") (pin "0") (pinfunction "TP_0") (pintype "power_in"))
      (node (ref "U7") (pin "5") (pinfunction "A0_5") (pintype "input"))
      (node (ref "U7") (pin "6") (pinfunction "DGND_6") (pintype "power_in"))
      (node (ref "U7") (pin "8") (pinfunction "AGND_&_TP_8") (pintype "power_in"))
      (node (ref "U8") (pin "0") (pinfunction "TP_0") (pintype "power_in"))
      (node (ref "U8") (pin "11") (pinfunction "GND_&_TP_11") (pintype "power_in"))
      (node (ref "U9") (pin "0") (pinfunction "TP_0") (pintype "power_in"))
      (node (ref "U9") (pin "11") (pinfunction "GND_&_TP_11") (pintype "power_in"))
    )
    (net (code "73") (name "Net-(D2-PadA)") (class "Default")
      (node (ref "D2") (pin "A") (pinfunction "A_A") (pintype "passive"))
      (node (ref "R17") (pin "8") (pinfunction "8_8") (pintype "passive"))
    )
    (net (code "74") (name "Net-(D3-PadA)") (class "Default")
      (node (ref "D3") (pin "A") (pinfunction "A_A") (pintype "passive"))
      (node (ref "R17") (pin "7") (pinfunction "7_7") (pintype "passive"))
    )
    (net (code "75") (name "Net-(D4-PadA)") (class "Default")
      (node (ref "D4") (pin "A") (pinfunction "A_A") (pintype "passive"))
      (node (ref "R17") (pin "6") (pinfunction "6_6") (pintype "passive"))
    )
    (net (code "76") (name "Net-(D5-PadA)") (class "Default")
      (node (ref "D5") (pin "A") (pinfunction "A_A") (pintype "passive"))
      (node (ref "R17") (pin "5") (pinfunction "5_5") (pintype "passive"))
    )
    (net (code "77") (name "Net-(D6-PadA)") (class "Default")
      (node (ref "D6") (pin "A") (pinfunction "A_A") (pintype "passive"))
      (node (ref "R18") (pin "8") (pinfunction "8_8") (pintype "passive"))
    )
    (net (code "78") (name "Net-(D7-PadA)") (class "Default")
      (node (ref "D7") (pin "A") (pinfunction "A_A") (pintype "passive"))
      (node (ref "R18") (pin "7") (pinfunction "7_7") (pintype "passive"))
    )
    (net (code "79") (name "Net-(D8-PadA)") (class "Default")
      (node (ref "D8") (pin "A") (pinfunction "A_A") (pintype "passive"))
      (node (ref "R18") (pin "6") (pinfunction "6_6") (pintype "passive"))
    )
    (net (code "80") (name "Net-(D9-PadA)") (class "Default")
      (node (ref "D9") (pin "A") (pinfunction "A_A") (pintype "passive"))
      (node (ref "R18") (pin "5") (pinfunction "5_5") (pintype "passive"))
    )
    (net (code "81") (name "Net-(JP1-Pad2)") (class "Default")
      (node (ref "JP1") (pin "2") (pinfunction "2_2") (pintype "passive"))
      (node (ref "R19") (pin "1") (pinfunction "1_1") (pintype "passive"))
    )
    (net (code "82") (name "Net-(U7-ADCIN)") (class "Default")
      (node (ref "U7") (pin "13") (pinfunction "MUXOUT_13") (pintype "output"))
      (node (ref "U7") (pin "14") (pinfunction "ADCIN_14") (pintype "input"))
    )
    (net (code "83") (name "Net-(U7-AVDD)") (class "Default")
      (node (ref "C41") (pin "2") (pinfunction "2_2") (pintype "passive"))
      (node (ref "C46") (pin "1") (pinfunction "1_1") (pintype "passive"))
      (node (ref "R19") (pin "2") (pinfunction "2_2") (pintype "passive"))
      (node (ref "U7") (pin "15") (pinfunction "AVDD_15") (pintype "power_in"))
    )
    (net (code "84") (name "Power") (class "Default")
      (node (ref "J5") (pin "8") (pinfunction "8_8") (pintype "passive"))
    )
    (net (code "85") (name "unconnected-(J5-Pad1)") (class "Default")
      (node (ref "J5") (pin "1") (pinfunction "1_1") (pintype "passive+no_connect"))
    )
    (net (code "86") (name "unconnected-(U7-PWRCON-Pad7)") (class "Default")
      (node (ref "U7") (pin "7") (pinfunction "PWRCON_7") (pintype "output+no_connect"))
    )
    (net (code "87") (name "unconnected-(U8-A1-Pad1)") (class "Default")
      (node (ref "U8") (pin "1") (pinfunction "A1_1") (pintype "bidirectional+no_connect"))
    )
    (net (code "88") (name "unconnected-(U8-A2-Pad3)") (class "Default")
      (node (ref "U8") (pin "3") (pinfunction "A2_3") (pintype "bidirectional+no_connect"))
    )
    (net (code "89") (name "unconnected-(U8-B1-Pad20)") (class "Default")
      (node (ref "U8") (pin "20") (pinfunction "B1_20") (pintype "bidirectional+no_connect"))
    )
    (net (code "90") (name "unconnected-(U8-B2-Pad18)") (class "Default")
      (node (ref "U8") (pin "18") (pinfunction "B2_18") (pintype "bidirectional+no_connect"))
    )
  )
)
